# H-BRIDGE.net
KiCad netlist of a schematic drawn in Altium Designer
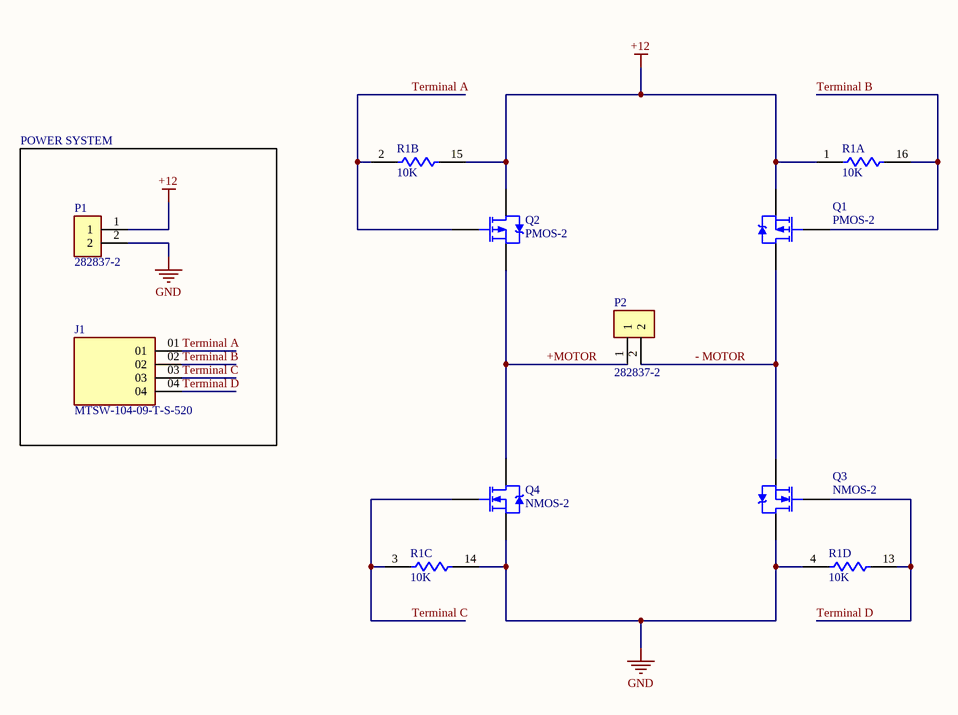
[diagram p0: H-BRIDGE.SchDoc]

(export (version "E")
  (design (tool "Eeschema 10.0.6"))
  (components
    (comp (ref "J1")
      (value "MTSW-104-09-T-S-520")
      (footprint "SAMTEC_MTSW-104-09-T-S-520")
      (libsource (lib "MTSW-104-09-T-S-520") (part "MTSW-104-09-T-S-520"))
    )
    (comp (ref "P1")
      (value "282837-2")
      (footprint "TE_282837-2")
      (fields (field (name "MF") "TE Connectivity"))
      (libsource (lib "") (part "282837-2_1"))
    )
    (comp (ref "P2")
      (value "282837-2")
      (footprint "TE_282837-2")
      (fields (field (name "MF") "TE Connectivity"))
      (libsource (lib "282837-2") (part "282837-2"))
    )
    (comp (ref "Q1")
      (value "PMOS-2")
      (footprint "TO-220AB")
      (description "P-Channel Power MOSFET")
      (fields (field (name "PUBLISHER") "Altium Limited"))
      (libsource (lib "Miscellaneous Devices") (part "PMOS-2"))
    )
    (comp (ref "Q2")
      (value "PMOS-2")
      (footprint "TO-220AB")
      (description "P-Channel Power MOSFET")
      (fields (field (name "PUBLISHER") "Altium Limited"))
      (libsource (lib "Miscellaneous Devices") (part "PMOS-2"))
    )
    (comp (ref "Q3")
      (value "NMOS-2")
      (footprint "TO-220AB")
      (description "N-Channel Power MOSFET")
      (fields (field (name "PUBLISHER") "Altium Limited"))
      (libsource (lib "Miscellaneous Devices") (part "NMOS-2"))
    )
    (comp (ref "Q4")
      (value "NMOS-2")
      (footprint "TO-220AB")
      (description "N-Channel Power MOSFET")
      (fields (field (name "PUBLISHER") "Altium Limited"))
      (libsource (lib "Miscellaneous Devices") (part "NMOS-2"))
    )
    (comp (ref "R1")
      (value "10K")
      (footprint "SOIC16_N")
      (description "Isolated Resistor Network - Parts")
      (fields (field (name "Comment") "Res Pack1") (field (name "PUBLISHER") "Altium Limited"))
      (libsource (lib "Miscellaneous Devices") (part "Res Pack1"))
    )
  )
  (nets
    (net (code "1") (name "+12") (class "Default")
      (node (ref "P1") (pin "1") (pinfunction "1_1") (pintype "passive"))
      (node (ref "Q1") (pin "3") (pinfunction "S_3") (pintype "passive"))
      (node (ref "Q2") (pin "2") (pinfunction "D_2") (pintype "passive"))
      (node (ref "R1") (pin "1") (pinfunction "1_1") (pintype "passive"))
      (node (ref "R1") (pin "15") (pinfunction "15_15") (pintype "passive"))
    )
    (net (code "2") (name "/+MOTOR") (class "Default")
      (node (ref "P2") (pin "1") (pinfunction "1_1") (pintype "passive"))
      (node (ref "Q2") (pin "3") (pinfunction "S_3") (pintype "passive"))
      (node (ref "Q4") (pin "2") (pinfunction "D_2") (pintype "passive"))
    )
    (net (code "3") (name "/- MOTOR") (class "Default")
      (node (ref "P2") (pin "2") (pinfunction "2_2") (pintype "passive"))
      (node (ref "Q1") (pin "2") (pinfunction "D_2") (pintype "passive"))
      (node (ref "Q3") (pin "3") (pinfunction "S_3") (pintype "passive"))
    )
    (net (code "4") (name "/Terminal A") (class "Default")
      (node (ref "J1") (pin "01") (pinfunction "01_01") (pintype "passive"))
      (node (ref "Q2") (pin "1") (pinfunction "G_1") (pintype "passive"))
      (node (ref "R1") (pin "2") (pinfunction "2_2") (pintype "passive"))
    )
    (net (code "5") (name "/Terminal B") (class "Default")
      (node (ref "J1") (pin "02") (pinfunction "02_02") (pintype "passive"))
      (node (ref "Q1") (pin "1") (pinfunction "G_1") (pintype "passive"))
      (node (ref "R1") (pin "16") (pinfunction "16_16") (pintype "passive"))
    )
    (net (code "6") (name "/Terminal C") (class "Default")
      (node (ref "J1") (pin "03") (pinfunction "03_03") (pintype "passive"))
      (node (ref "Q4") (pin "1") (pinfunction "G_1") (pintype "passive"))
      (node (ref "R1") (pin "3") (pinfunction "3_3") (pintype "passive"))
    )
    (net (code "7") (name "/Terminal D") (class "Default")
      (node (ref "J1") (pin "04") (pinfunction "04_04") (pintype "passive"))
      (node (ref "Q3") (pin "1") (pinfunction "G_1") (pintype "passive"))
      (node (ref "R1") (pin "13") (pinfunction "13_13") (pintype "passive"))
    )
    (net (code "8") (name "GND") (class "Default")
      (node (ref "P1") (pin "2") (pinfunction "2_2") (pintype "passive"))
      (node (ref "Q3") (pin "2") (pinfunction "D_2") (pintype "passive"))
      (node (ref "Q4") (pin "3") (pinfunction "S_3") (pintype "passive"))
      (node (ref "R1") (pin "14") (pinfunction "14_14") (pintype "passive"))
      (node (ref "R1") (pin "4") (pinfunction "4_4") (pintype "passive"))
    )
  )
)
